# STeaMi-FP2-Chargeur_de_batterie.net
KiCad netlist of a schematic drawn in Altium Designer
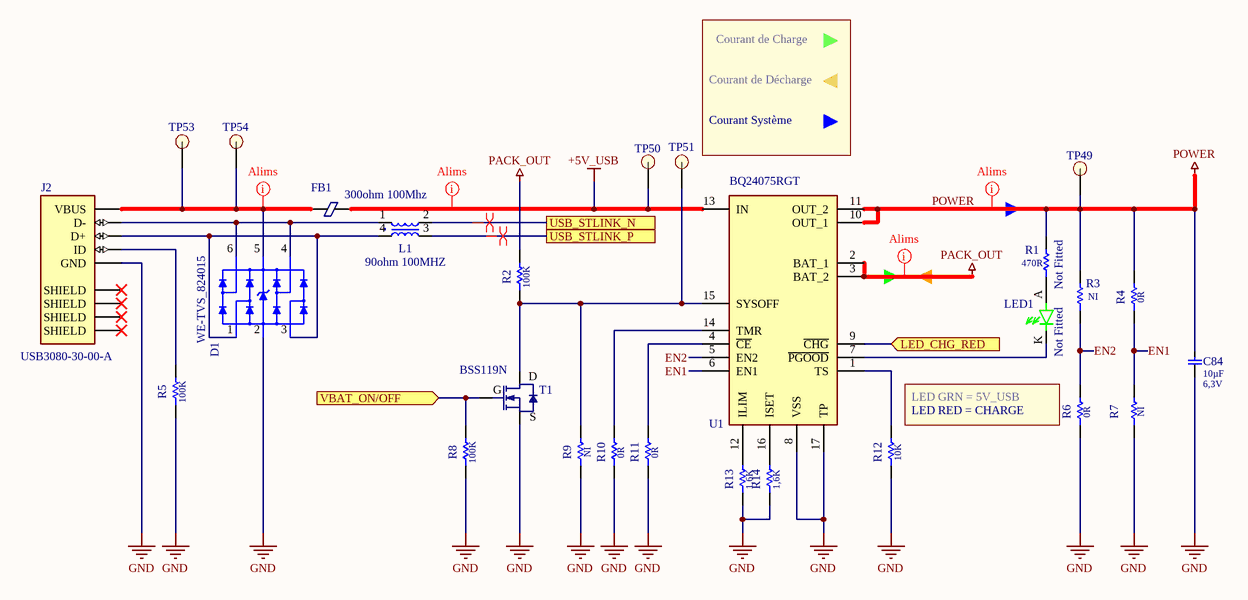
[diagram p0: STeaMi-FP2-Chargeur_de_batterie.SchDoc]

(export (version "E")
  (design (tool "Eeschema 10.0.6"))
  (components
    (comp (ref "C84")
      (value "~")
      (footprint "0402-CAP")
      (description "CAP CER 10µF 6,3V X5R 0402")
      (fields
        (field (name "MANUFACTURER") "Murata")
        (field (name "MANUFACTURER PART NUMBER") "GRM155R60J106ME15D")
        (field (name "CAPACITANCE") "10µF")
        (field (name "VOLTAGE") "6,3V")
        (field (name "CREATED BY") "EAG")
        (field (name "CHECKED BY") "*")
      )
      (libsource (lib "ComponentDB") (part "CAP_SYMBOL"))
    )
    (comp (ref "D1")
      (value "~")
      (footprint "WE-TVS_SOT23-6L")
      (description "Suppresseurs ESD / diodes TVS WE-TVS High Speed 5uA 5VDC 4+1")
      (fields
        (field (name "MANUFACTURER") "Wurth")
        (field (name "MANUFACTURER PART NUMBER") "WE-TVS_824015")
        (field (name "PART NUMBER") "WE-TVS_824015")
        (field (name "CREATED BY") "EAG")
      )
      (libsource (lib "ComponentDB") (part "WE-TVS_824015"))
    )
    (comp (ref "FB1")
      (value "300ohm 100Mhz")
      (footprint "INDC1608X80N")
      (description "Chip Ferrite Bead 300 ohm à 100MHZ")
      (fields
        (field (name "MANUFACTURER") "WURTH")
        (field (name "MANUFACTURER PART NUMBER") "742792641")
        (field (name "CREATED BY") "EAG")
        (field (name "CHECKED BY") "*")
      )
      (libsource (lib "ComponentDB") (part "EMI_SYMBOL"))
    )
    (comp (ref "J2")
      (value "~")
      (footprint "USB3080-30-00-A")
      (description "Connector micro USB Bottom-SMT No Peg")
      (fields
        (field (name "MANUFACTURER") "GCT")
        (field (name "MANUFACTURER PART NUMBER") "USB3080-30-00-A")
        (field (name "PART NUMBER") "USB3080-30-00-A")
        (field (name "CHECKED BY") "*")
        (field (name "CREATED BY") "EAG")
      )
      (libsource (lib "ComponentDB") (part "USB3080-30-00-A"))
    )
    (comp (ref "L1")
      (value "90ohm 100MHZ")
      (footprint "WE-CNSW_06038")
      (description "Common mode chokes")
      (fields
        (field (name "MANUFACTURER") "WURTH")
        (field (name "MANUFACTURER PART NUMBER") "744230900")
        (field (name "CREATED BY") "EAG")
      )
      (libsource (lib "ComponentDB") (part "BOB_MOD_COMMUN_SYMBOL"))
    )
    (comp (ref "LED1")
      (value "~")
      (footprint "APTD1608LZGCK-G")
      (description "LED GREEN 2V 20mA 0603 SMD")
      (fields
        (field (name "MANUFACTURER") "WURTH")
        (field (name "MANUFACTURER PART NUMBER") "150060VS75000")
        (field (name "FITTED") "Not Fitted")
        (field (name "CREATED BY") "EAG")
      )
      (libsource (lib "ComponentDB") (part "LED_GREEN_SYMBOL"))
    )
    (comp (ref "R1")
      (value "Not Fitted")
      (footprint "RESC1005X40N_0402")
      (description "RES CMS 470R5%-0,1W-0402 ±200ppm/°C")
      (fields
        (field (name "MANUFACTURER") "Panasonic")
        (field (name "MANUFACTURER PART NUMBER") "ERJ-2GEJ471X")
        (field (name "RESISTANCE") "470R")
        (field (name "CREATED BY") "EAG")
      )
      (libsource (lib "ComponentDB") (part "RES_SYMBOL"))
    )
    (comp (ref "R2")
      (value "~")
      (footprint "RESC1005X40N_0402")
      (description "RES CMS 100K5%-0,0625W-0402 ±100ppm/°C")
      (fields
        (field (name "MANUFACTURER") "Yageo")
        (field (name "MANUFACTURER PART NUMBER") "RC0402JR-07100KL")
        (field (name "RESISTANCE") "100K")
        (field (name "CREATED BY") "EAG")
      )
      (libsource (lib "ComponentDB") (part "RES_SYMBOL"))
    )
    (comp (ref "R3")
      (value "~")
      (footprint "RESC1005X40N_0402")
      (description "NI")
      (fields
        (field (name "POWER") "0,1")
        (field (name "RESISTANCE") "NI")
        (field (name "PART NUMBER") "NI-1%-0,1W-0603")
        (field (name "CREATED BY") "MSA")
      )
      (libsource (lib "ComponentDB") (part "RES_SYMBOL"))
    )
    (comp (ref "R4")
      (value "~")
      (footprint "RESC1005X40N_0402")
      (description "RES CMS 0R5%-0,0625W-0402")
      (fields
        (field (name "MANUFACTURER") "Yageo")
        (field (name "MANUFACTURER PART NUMBER") "RC0402JR-100RL")
        (field (name "RESISTANCE") "0R")
        (field (name "CREATED BY") "EAG")
      )
      (libsource (lib "ComponentDB") (part "RES_SYMBOL"))
    )
    (comp (ref "R5")
      (value "~")
      (footprint "RESC1005X40N_0402")
      (description "RES CMS 100K5%-0,0625W-0402 ±100ppm/°C")
      (fields
        (field (name "MANUFACTURER") "Yageo")
        (field (name "MANUFACTURER PART NUMBER") "RC0402JR-07100KL")
        (field (name "RESISTANCE") "100K")
        (field (name "CREATED BY") "EAG")
      )
      (libsource (lib "ComponentDB") (part "RES_SYMBOL"))
    )
    (comp (ref "R6")
      (value "~")
      (footprint "RESC1005X40N_0402")
      (description "RES CMS 0R5%-0,0625W-0402")
      (fields
        (field (name "MANUFACTURER") "Yageo")
        (field (name "MANUFACTURER PART NUMBER") "RC0402JR-100RL")
        (field (name "RESISTANCE") "0R")
        (field (name "CREATED BY") "EAG")
      )
      (libsource (lib "ComponentDB") (part "RES_SYMBOL"))
    )
    (comp (ref "R7")
      (value "~")
      (footprint "RESC1005X40N_0402")
      (description "NI")
      (fields
        (field (name "POWER") "0,1")
        (field (name "RESISTANCE") "NI")
        (field (name "PART NUMBER") "NI-1%-0,1W-0603")
        (field (name "CREATED BY") "MSA")
      )
      (libsource (lib "ComponentDB") (part "RES_SYMBOL"))
    )
    (comp (ref "R8")
      (value "~")
      (footprint "RESC1005X40N_0402")
      (description "RES CMS 100K5%-0,0625W-0402 ±100ppm/°C")
      (fields
        (field (name "MANUFACTURER") "Yageo")
        (field (name "MANUFACTURER PART NUMBER") "RC0402JR-07100KL")
        (field (name "RESISTANCE") "100K")
        (field (name "CREATED BY") "EAG")
      )
      (libsource (lib "ComponentDB") (part "RES_SYMBOL"))
    )
    (comp (ref "R9")
      (value "~")
      (footprint "RESC1005X40N_0402")
      (description "NI")
      (fields
        (field (name "POWER") "0,1")
        (field (name "RESISTANCE") "NI")
        (field (name "PART NUMBER") "NI-1%-0,1W-0603")
        (field (name "CREATED BY") "MSA")
      )
      (libsource (lib "ComponentDB") (part "RES_SYMBOL"))
    )
    (comp (ref "R10")
      (value "~")
      (footprint "RESC1005X40N_0402")
      (description "RES CMS 0R5%-0,0625W-0402")
      (fields
        (field (name "MANUFACTURER") "Yageo")
        (field (name "MANUFACTURER PART NUMBER") "RC0402JR-100RL")
        (field (name "RESISTANCE") "0R")
        (field (name "CREATED BY") "EAG")
      )
      (libsource (lib "ComponentDB") (part "RES_SYMBOL"))
    )
    (comp (ref "R11")
      (value "~")
      (footprint "RESC1005X40N_0402")
      (description "RES CMS 0R5%-0,0625W-0402")
      (fields
        (field (name "MANUFACTURER") "Yageo")
        (field (name "MANUFACTURER PART NUMBER") "RC0402JR-100RL")
        (field (name "RESISTANCE") "0R")
        (field (name "CREATED BY") "EAG")
      )
      (libsource (lib "ComponentDB") (part "RES_SYMBOL"))
    )
    (comp (ref "R12")
      (value "~")
      (footprint "RESC1005X40N_0402")
      (description "RES CMS 10K1%-0,0625W-0402 ±100ppm/°C")
      (fields
        (field (name "MANUFACTURER") "Yageo")
        (field (name "MANUFACTURER PART NUMBER") "AC0402FR-1310KL")
        (field (name "RESISTANCE") "10K")
        (field (name "CREATED BY") "EAG")
      )
      (libsource (lib "ComponentDB") (part "RES_SYMBOL"))
    )
    (comp (ref "R13")
      (value "~")
      (footprint "RESC1005X40N_0402")
      (description "RES CMS 1,6K1%-0,1W-0402 ±100ppm/°C")
      (fields
        (field (name "MANUFACTURER") "Panasonic")
        (field (name "MANUFACTURER PART NUMBER") "ERJ-2RKF 1601X")
        (field (name "RESISTANCE") "1,6K")
        (field (name "CREATED BY") "EAG")
      )
      (libsource (lib "ComponentDB") (part "RES_SYMBOL"))
    )
    (comp (ref "R14")
      (value "~")
      (footprint "RESC1005X40N_0402")
      (description "RES CMS 1,6K1%-0,1W-0402 ±100ppm/°C")
      (fields
        (field (name "MANUFACTURER") "Panasonic")
        (field (name "MANUFACTURER PART NUMBER") "ERJ-2RKF 1601X")
        (field (name "RESISTANCE") "1,6K")
        (field (name "CREATED BY") "EAG")
      )
      (libsource (lib "ComponentDB") (part "RES_SYMBOL"))
    )
    (comp (ref "T1")
      (value "~")
      (footprint "SOT95P260X110-3N_SOT-23-3")
      (description "Small-Signal-Transitor MOSFET N")
      (fields
        (field (name "MANUFACTURER") "Infineon")
        (field (name "MANUFACTURER PART NUMBER") "BSS119N-H6327")
        (field (name "PART NUMBER") "BSS119N")
        (field (name "CHECKED BY") "MSA")
        (field (name "CREATED BY") "EAG")
      )
      (libsource (lib "ComponentDB") (part "BSS119N"))
    )
    (comp (ref "TP49")
      (value "PAD")
      (footprint "Testpoint 1mm")
      (description "TESTPOINTPAD")
      (fields
        (field (name "MANUFACTURER") "Smartembed")
        (field (name "MANUFACTURER PART NUMBER") "TESTPOINT")
        (field (name "CREATED BY") "EAG")
      )
      (libsource (lib "ComponentDB") (part "TESTPOINT"))
    )
    (comp (ref "TP50")
      (value "PAD")
      (footprint "Testpoint 1mm")
      (description "TESTPOINTPAD")
      (fields
        (field (name "MANUFACTURER") "Smartembed")
        (field (name "MANUFACTURER PART NUMBER") "TESTPOINT")
        (field (name "CREATED BY") "EAG")
      )
      (libsource (lib "ComponentDB") (part "TESTPOINT"))
    )
    (comp (ref "TP51")
      (value "PAD")
      (footprint "Testpoint 1mm")
      (description "TESTPOINTPAD")
      (fields
        (field (name "MANUFACTURER") "Smartembed")
        (field (name "MANUFACTURER PART NUMBER") "TESTPOINT")
        (field (name "CREATED BY") "EAG")
      )
      (libsource (lib "ComponentDB") (part "TESTPOINT"))
    )
    (comp (ref "TP53")
      (value "PAD")
      (footprint "Testpoint 1mm")
      (description "TESTPOINTPAD")
      (fields
        (field (name "MANUFACTURER") "Smartembed")
        (field (name "MANUFACTURER PART NUMBER") "TESTPOINT")
        (field (name "CREATED BY") "EAG")
      )
      (libsource (lib "ComponentDB") (part "TESTPOINT"))
    )
    (comp (ref "TP54")
      (value "PAD")
      (footprint "Testpoint 1mm")
      (description "TESTPOINTPAD")
      (fields
        (field (name "MANUFACTURER") "Smartembed")
        (field (name "MANUFACTURER PART NUMBER") "TESTPOINT")
        (field (name "CREATED BY") "EAG")
      )
      (libsource (lib "ComponentDB") (part "TESTPOINT"))
    )
    (comp (ref "U1")
      (value "~")
      (footprint "QFN50P300X300X100-17N")
      (description "Standalone 1 cell 1,5A batterry with PowerPath")
      (fields
        (field (name "MANUFACTURER") "Texas Instruments")
        (field (name "MANUFACTURER PART NUMBER") "BQ24075RGT")
        (field (name "PART NUMBER") "BQ24075RGT")
        (field (name "CREATED BY") "EAG")
        (field (name "CHECKED BY") "*")
      )
      (libsource (lib "ComponentDB") (part "BQ24075RGT"))
    )
  )
  (nets
    (net (code "1") (name "+5V_USB") (class "Default")
      (node (ref "FB1") (pin "2") (pinfunction "2_2") (pintype "passive"))
      (node (ref "TP50") (pin "1") (pinfunction "1_1") (pintype "passive"))
      (node (ref "U1") (pin "13") (pinfunction "IN_13") (pintype "passive"))
    )
    (net (code "2") (name "/EN1") (class "Default")
      (node (ref "R4") (pin "1") (pinfunction "1_1") (pintype "passive"))
      (node (ref "R7") (pin "2") (pinfunction "2_2") (pintype "passive"))
      (node (ref "U1") (pin "6") (pinfunction "EN1_6") (pintype "passive"))
    )
    (net (code "3") (name "/EN2") (class "Default")
      (node (ref "R3") (pin "1") (pinfunction "1_1") (pintype "passive"))
      (node (ref "R6") (pin "2") (pinfunction "2_2") (pintype "passive"))
      (node (ref "U1") (pin "5") (pinfunction "EN2_5") (pintype "passive"))
    )
    (net (code "4") (name "/LED_CHG_RED") (class "Default")
      (node (ref "U1") (pin "9") (pinfunction "~{CHG}_9") (pintype "passive"))
    )
    (net (code "5") (name "/USB_STLINK_N") (class "Default")
      (node (ref "L1") (pin "2") (pinfunction "2_2") (pintype "passive"))
    )
    (net (code "6") (name "/USB_STLINK_P") (class "Default")
      (node (ref "L1") (pin "3") (pinfunction "3_3") (pintype "passive"))
    )
    (net (code "7") (name "/VBAT_ON{slash}OFF") (class "Default")
      (node (ref "R8") (pin "2") (pinfunction "2_2") (pintype "passive"))
      (node (ref "T1") (pin "1") (pinfunction "GATE_1") (pintype "passive"))
    )
    (net (code "8") (name "GND") (class "Default")
      (node (ref "C84") (pin "1") (pinfunction "1_1") (pintype "passive"))
      (node (ref "D1") (pin "2") (pinfunction "GND_2") (pintype "power_in"))
      (node (ref "J2") (pin "5") (pinfunction "GND_5") (pintype "power_in"))
      (node (ref "R10") (pin "1") (pinfunction "1_1") (pintype "passive"))
      (node (ref "R11") (pin "1") (pinfunction "1_1") (pintype "passive"))
      (node (ref "R12") (pin "1") (pinfunction "1_1") (pintype "passive"))
      (node (ref "R13") (pin "1") (pinfunction "1_1") (pintype "passive"))
      (node (ref "R14") (pin "1") (pinfunction "1_1") (pintype "passive"))
      (node (ref "R5") (pin "1") (pinfunction "1_1") (pintype "passive"))
      (node (ref "R6") (pin "1") (pinfunction "1_1") (pintype "passive"))
      (node (ref "R7") (pin "1") (pinfunction "1_1") (pintype "passive"))
      (node (ref "R8") (pin "1") (pinfunction "1_1") (pintype "passive"))
      (node (ref "R9") (pin "1") (pinfunction "1_1") (pintype "passive"))
      (node (ref "T1") (pin "2") (pinfunction "SOURCE_2") (pintype "passive"))
      (node (ref "U1") (pin "17") (pinfunction "TP_17") (pintype "passive"))
      (node (ref "U1") (pin "8") (pinfunction "VSS_8") (pintype "passive"))
    )
    (net (code "9") (name "Net-(D1-VDD)") (class "Default")
      (node (ref "D1") (pin "5") (pinfunction "VDD_5") (pintype "power_in"))
      (node (ref "FB1") (pin "1") (pinfunction "1_1") (pintype "passive"))
      (node (ref "J2") (pin "1") (pinfunction "VBUS_1") (pintype "power_in"))
      (node (ref "TP53") (pin "1") (pinfunction "1_1") (pintype "passive"))
      (node (ref "TP54") (pin "1") (pinfunction "1_1") (pintype "passive"))
    )
    (net (code "10") (name "Net-(J2-D+)") (class "Default")
      (node (ref "D1") (pin "1") (pinfunction "1_1") (pintype "passive"))
      (node (ref "D1") (pin "3") (pinfunction "3_3") (pintype "passive"))
      (node (ref "J2") (pin "3") (pinfunction "D+_3") (pintype "bidirectional"))
      (node (ref "L1") (pin "4") (pinfunction "4_4") (pintype "passive"))
    )
    (net (code "11") (name "Net-(J2-D-)") (class "Default")
      (node (ref "D1") (pin "4") (pinfunction "4_4") (pintype "passive"))
      (node (ref "D1") (pin "6") (pinfunction "6_6") (pintype "passive"))
      (node (ref "J2") (pin "2") (pinfunction "D-_2") (pintype "bidirectional"))
      (node (ref "L1") (pin "1") (pinfunction "1_1") (pintype "passive"))
    )
    (net (code "12") (name "Net-(J2-ID)") (class "Default")
      (node (ref "J2") (pin "4") (pinfunction "ID_4") (pintype "bidirectional"))
      (node (ref "R5") (pin "2") (pinfunction "2_2") (pintype "passive"))
    )
    (net (code "13") (name "Net-(LED1-PadA)") (class "Default")
      (node (ref "LED1") (pin "A") (pinfunction "A_A") (pintype "passive"))
      (node (ref "R1") (pin "1") (pinfunction "1_1") (pintype "passive"))
    )
    (net (code "14") (name "Net-(T1-DRAIN)") (class "Default")
      (node (ref "R2") (pin "1") (pinfunction "1_1") (pintype "passive"))
      (node (ref "R9") (pin "2") (pinfunction "2_2") (pintype "passive"))
      (node (ref "T1") (pin "3") (pinfunction "DRAIN_3") (pintype "passive"))
      (node (ref "TP51") (pin "1") (pinfunction "1_1") (pintype "passive"))
      (node (ref "U1") (pin "15") (pinfunction "SYSOFF_15") (pintype "passive"))
    )
    (net (code "15") (name "Net-(U1-ILIM)") (class "Default")
      (node (ref "R13") (pin "2") (pinfunction "2_2") (pintype "passive"))
      (node (ref "U1") (pin "12") (pinfunction "ILIM_12") (pintype "passive"))
    )
    (net (code "16") (name "Net-(U1-ISET)") (class "Default")
      (node (ref "R14") (pin "2") (pinfunction "2_2") (pintype "passive"))
      (node (ref "U1") (pin "16") (pinfunction "ISET_16") (pintype "passive"))
    )
    (net (code "17") (name "Net-(U1-TMR)") (class "Default")
      (node (ref "R10") (pin "2") (pinfunction "2_2") (pintype "passive"))
      (node (ref "U1") (pin "14") (pinfunction "TMR_14") (pintype "passive"))
    )
    (net (code "18") (name "Net-(U1-TS)") (class "Default")
      (node (ref "R12") (pin "2") (pinfunction "2_2") (pintype "passive"))
      (node (ref "U1") (pin "1") (pinfunction "TS_1") (pintype "passive"))
    )
    (net (code "19") (name "Net-(U1-~{CE})") (class "Default")
      (node (ref "R11") (pin "2") (pinfunction "2_2") (pintype "passive"))
      (node (ref "U1") (pin "4") (pinfunction "~{CE}_4") (pintype "passive"))
    )
    (net (code "20") (name "Net-(U1-~{PGOOD})") (class "Default")
      (node (ref "LED1") (pin "K") (pinfunction "K_K") (pintype "passive"))
      (node (ref "U1") (pin "7") (pinfunction "~{PGOOD}_7") (pintype "passive"))
    )
    (net (code "21") (name "PACK_OUT") (class "Default")
      (node (ref "R2") (pin "2") (pinfunction "2_2") (pintype "passive"))
      (node (ref "U1") (pin "2") (pinfunction "BAT_1_2") (pintype "passive"))
      (node (ref "U1") (pin "3") (pinfunction "BAT_2_3") (pintype "passive"))
    )
    (net (code "22") (name "POWER") (class "Default")
      (node (ref "C84") (pin "2") (pinfunction "2_2") (pintype "passive"))
      (node (ref "R1") (pin "2") (pinfunction "2_2") (pintype "passive"))
      (node (ref "R3") (pin "2") (pinfunction "2_2") (pintype "passive"))
      (node (ref "R4") (pin "2") (pinfunction "2_2") (pintype "passive"))
      (node (ref "TP49") (pin "1") (pinfunction "1_1") (pintype "passive"))
      (node (ref "U1") (pin "10") (pinfunction "OUT_1_10") (pintype "passive"))
      (node (ref "U1") (pin "11") (pinfunction "OUT_2_11") (pintype "passive"))
    )
    (net (code "23") (name "unconnected-(J2-SHIELD-Pad6)") (class "Default")
      (node (ref "J2") (pin "6") (pinfunction "SHIELD_6") (pintype "power_in+no_connect"))
    )
    (net (code "24") (name "unconnected-(J2-SHIELD-Pad7)") (class "Default")
      (node (ref "J2") (pin "7") (pinfunction "SHIELD_7") (pintype "power_in+no_connect"))
    )
    (net (code "25") (name "unconnected-(J2-SHIELD-Pad8)") (class "Default")
      (node (ref "J2") (pin "8") (pinfunction "SHIELD_8") (pintype "power_in+no_connect"))
    )
    (net (code "26") (name "unconnected-(J2-SHIELD-Pad9)") (class "Default")
      (node (ref "J2") (pin "9") (pinfunction "SHIELD_9") (pintype "power_in+no_connect"))
    )
  )
)
